# CE842170047_SHEET3.net
KiCad netlist of a schematic drawn in Altium Designer
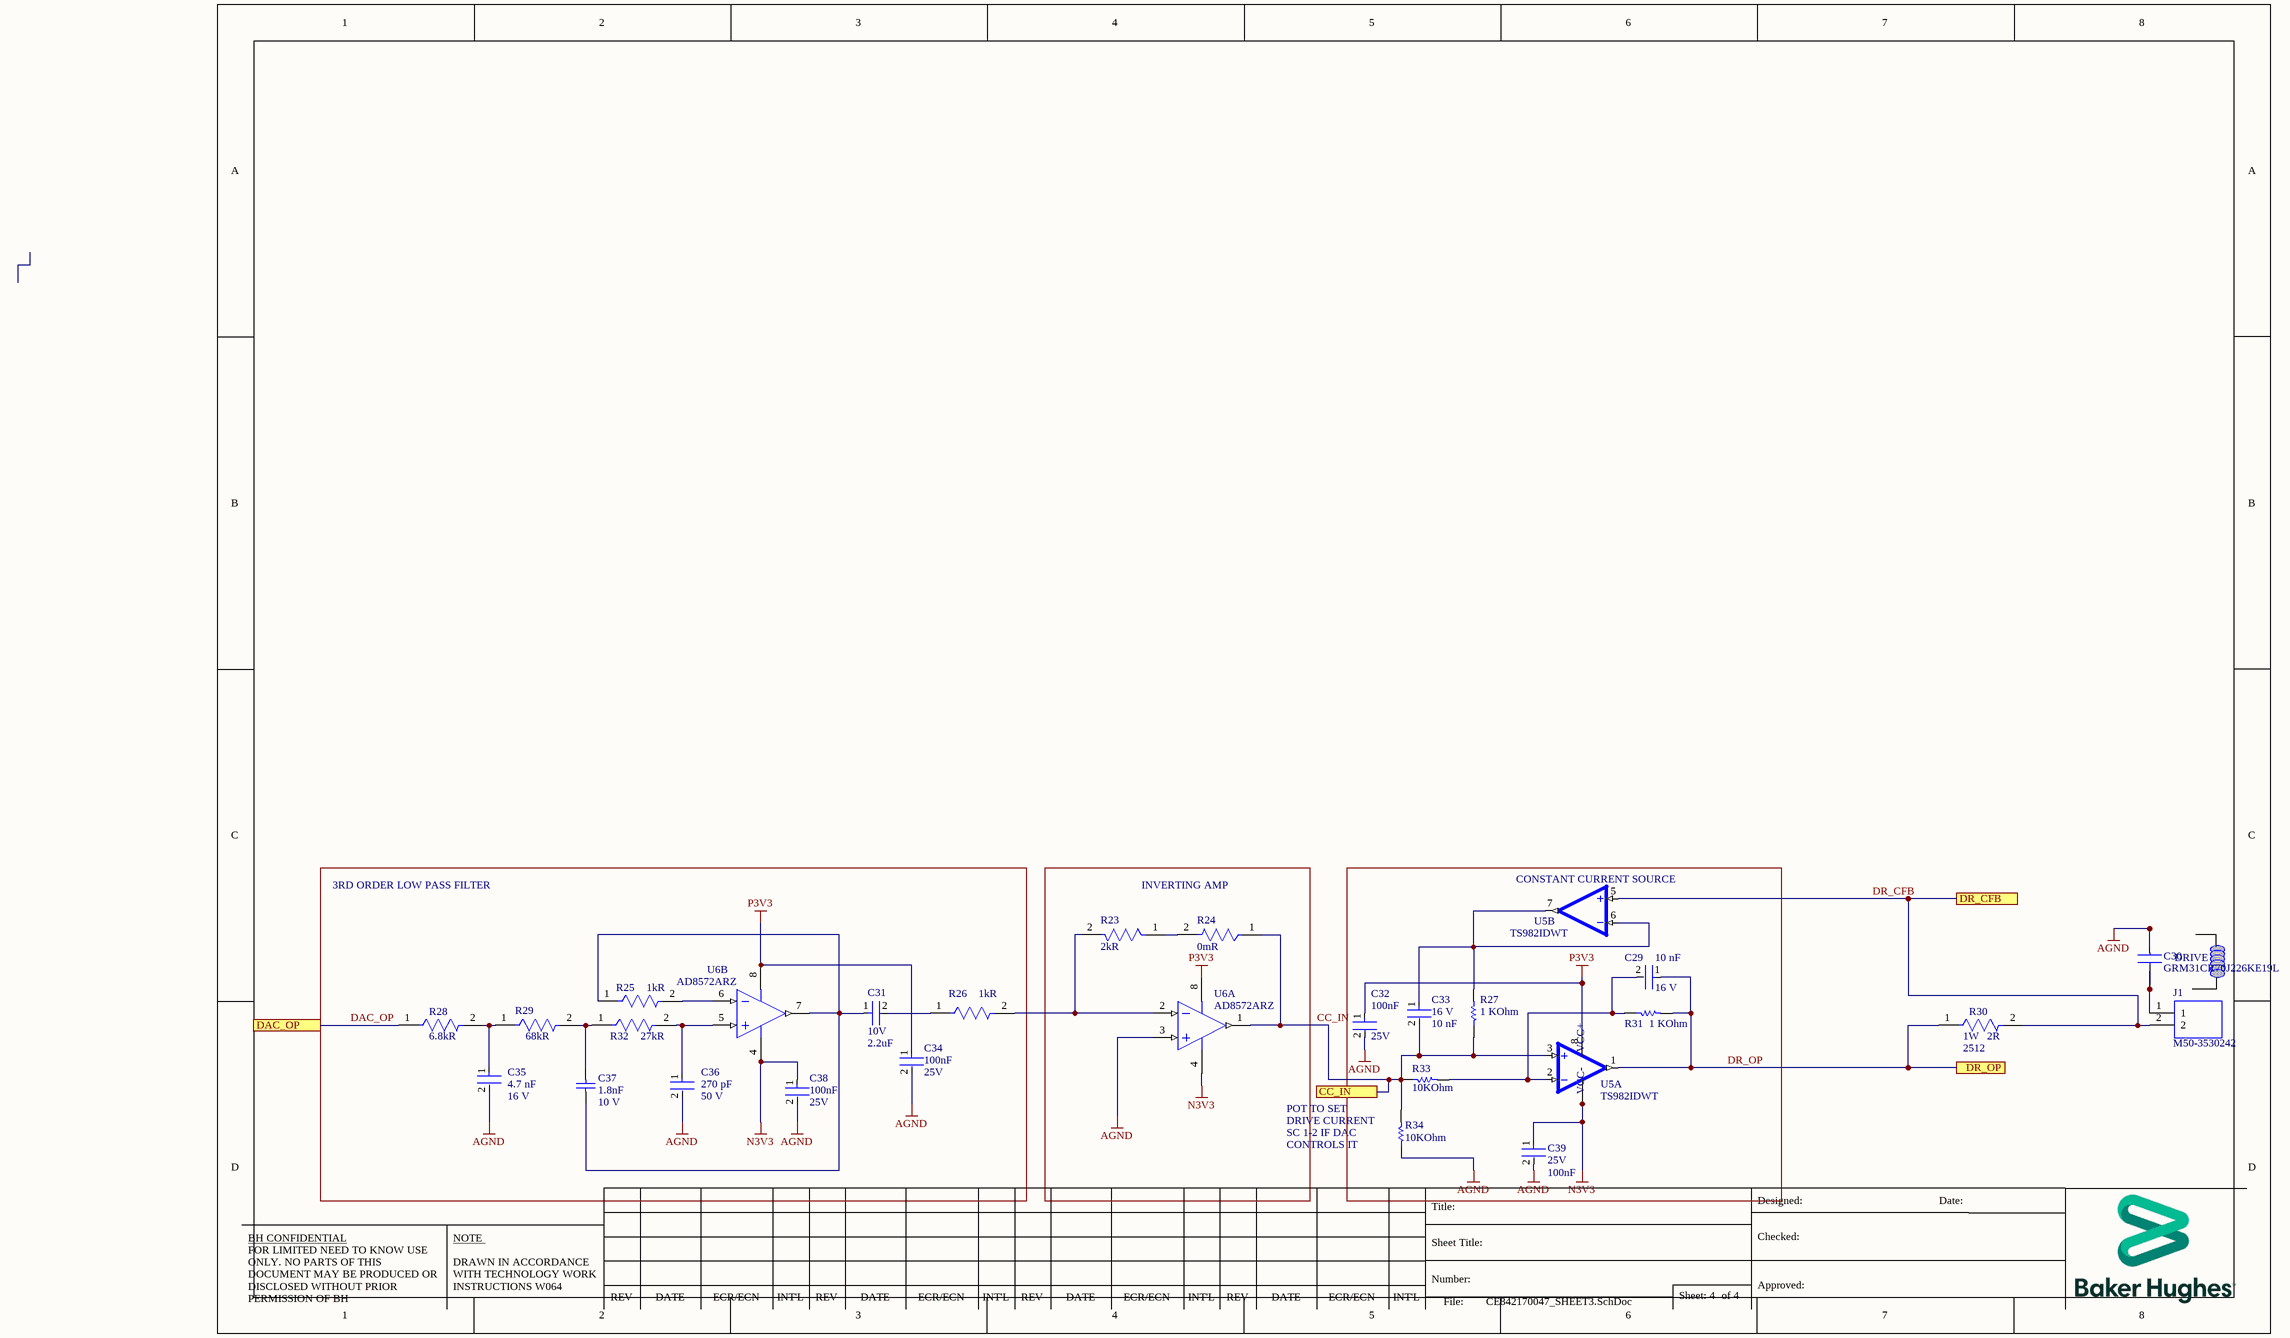
[diagram p0: CE842170047_SHEET3.SchDoc]

(export (version "E")
  (design (tool "Eeschema 10.0.6"))
  (components
    (comp (ref "C29")
      (value "CC0402KRX7R7BB103")
      (footprint "FP-CC0402-MFG")
      (description "CAP CER 10000PF 16V X7R 0402")
      (fields
        (field (name "CAPACITANCE") "10 nF")
        (field (name "TOLERANCE") "0.1")
        (field (name "VOLTAGE RATING") "16 V")
        (field (name "MANUFACTURER") "YAGEO")
      )
      (libsource (lib "Altium Content Vault") (part "11868f565c42a9108669ba33697ecf6"))
    )
    (comp (ref "C30")
      (value "GRM31CR70J226KE19L")
      (footprint "CAPC3216X180N")
      (description "Murata 1206 GRM 22uF Ceramic Multilayer Capacitor, 6.3 V dc, +125C, X7R Dielectric, +/-10% SMD")
      (fields (field (name "MOUSER PART NUMBER") "81-GRM31CR70J226KE9L"))
      (libsource (lib "GRM31CR70J226KE19L") (part "GRM31CR70J226KE19L"))
    )
    (comp (ref "C31")
      (value "CGB3B3X5R1A225M055AB")
      (footprint "FP-CGB3B-IPC_A")
      (description "Multilayer Ceramic Capacitors 2.2uF ±20% 10V X5R SMD 0603")
      (fields
        (field (name "VOLTAGE RATING") "10V")
        (field (name "TOLERANCE") "20%")
        (field (name "CAPACITANCE") "2.2uF")
      )
      (libsource (lib "Altium Content Vault") (part "b4654b650e69147ec39a6b967a45e02"))
    )
    (comp (ref "C32")
      (value "C1005X5R1E104K050BC")
      (footprint "FP-C1005-050-0_05-MFG")
      (description "Multilayer Ceramic Capacitors 100nF ±10% 25V X5R SMD 0402")
      (fields
        (field (name "VOLTAGE RATING (DC)") "25V")
        (field (name "CAPACITANCE") "100nF")
        (field (name "TOLERANCE") "10%")
        (field (name "VOLTAGE") "25V")
      )
      (libsource (lib "Altium Content Vault") (part "b4654b650e69147ec39a6b967a45e02"))
    )
    (comp (ref "C33")
      (value "CC0402KRX7R7BB103")
      (footprint "FP-CC0402-MFG")
      (description "CAP CER 10000PF 16V X7R 0402")
      (fields
        (field (name "CAPACITANCE") "10 nF")
        (field (name "TOLERANCE") "0.1")
        (field (name "VOLTAGE RATING") "16 V")
        (field (name "MANUFACTURER") "YAGEO")
      )
      (libsource (lib "Altium Content Vault") (part "11868f565c42a9108669ba33697ecf6"))
    )
    (comp (ref "C34")
      (value "C1005X5R1E104K050BC")
      (footprint "FP-C1005-050-0_05-MFG")
      (description "Multilayer Ceramic Capacitors 100nF ±10% 25V X5R SMD 0402")
      (fields
        (field (name "VOLTAGE RATING (DC)") "25V")
        (field (name "CAPACITANCE") "100nF")
        (field (name "TOLERANCE") "10%")
        (field (name "VOLTAGE") "25V")
      )
      (libsource (lib "Altium Content Vault") (part "b4654b650e69147ec39a6b967a45e02"))
    )
    (comp (ref "C35")
      (value "CC0402KRX7R7BB472")
      (footprint "FP-CC0402-MFG")
      (description "CAP CER 4700PF 16V X7R 0402")
      (fields
        (field (name "CAPACITANCE") "4.7 nF")
        (field (name "OCTOPART") "https://octopart.com/cc0402krx7r7bb472-yageo-44648962")
        (field (name "MANUFACTURER") "YAGEO")
        (field (name "VOLTAGE RATING") "16 V")
      )
      (libsource (lib "Altium Content Vault") (part "11868f565c42a9108669ba33697ecf6"))
    )
    (comp (ref "C36")
      (value "C0402C271K5RACTU")
      (footprint "FP-C0402-BB-MFG")
      (description "CAP CER 270PF 50V 10% X7R 0402")
      (fields
        (field (name "CAPACITANCE") "270 pF")
        (field (name "VOLTAGE RATING") "50 V")
        (field (name "MANUFACTURER") "Kemet")
        (field (name "OCTOPART") "https://octopart.com/c0402c271k5ractu-kemet-5510096")
      )
      (libsource (lib "Altium Content Vault") (part "b4654b650e69147ec39a6b967a45e02"))
    )
    (comp (ref "C37")
      (value "1.8nF")
      (footprint "CAPC0402(1005)60_N")
      (description "CAP 1.8nF 10V ±5% 0402 (1005 Metric) Thickness 0.6mm SMD")
      (fields
        (field (name "RATED VOLTAGE") "10 V")
        (field (name "TOLERANCE") "Â±5%")
        (field (name "Comment") "CAP 1.8nF 10V 0402(1005)")
      )
      (libsource (lib "Altium Content Vault") (part "CAP"))
    )
    (comp (ref "C38")
      (value "C1005X5R1E104K050BC")
      (footprint "FP-C1005-050-0_05-MFG")
      (description "Multilayer Ceramic Capacitors 100nF ±10% 25V X5R SMD 0402")
      (fields
        (field (name "VOLTAGE RATING (DC)") "25V")
        (field (name "CAPACITANCE") "100nF")
        (field (name "TOLERANCE") "10%")
        (field (name "VOLTAGE") "25V")
      )
      (libsource (lib "Altium Content Vault") (part "b4654b650e69147ec39a6b967a45e02"))
    )
    (comp (ref "C39")
      (value "C1005X5R1E104K050BC")
      (footprint "FP-C1005-050-0_05-MFG")
      (description "Multilayer Ceramic Capacitors 100nF ±10% 25V X5R SMD 0402")
      (fields
        (field (name "VOLTAGE RATING (DC)") "25V")
        (field (name "CAPACITANCE") "100nF")
        (field (name "TOLERANCE") "10%")
        (field (name "VOLTAGE") "25V")
      )
      (libsource (lib "Altium Content Vault") (part "b4654b650e69147ec39a6b967a45e02"))
    )
    (comp (ref "J1")
      (value "M50-3530242")
      (footprint "HDRV2W40P0X127_1X2_254X210X420P")
      (description "Headers & Wire Housings 2 WAY SIL VERT PC TAIL P/HDR")
      (fields (field (name "MOUSER PART NUMBER") "855-M50-3530242"))
      (libsource (lib "M50-3530242") (part "M50-3530242"))
    )
    (comp (ref "R23")
      (value "CRCW04022K00FKED")
      (footprint "FP-CRCW0402-e3-IPC_C")
      (description "RES Thick Film, 2kΩ, 1%, 0.063W, 100ppm/°C, 0402")
      (fields (field (name "TOLERANCE") "1%") (field (name "RESISTANCE") "2kR"))
      (libsource (lib "Altium Content Vault") (part "1029c3af85768c4190bb7ad29bc67b5"))
    )
    (comp (ref "R24")
      (value "MCS04020Z0000ZE000")
      (footprint "FP-MCS0402-MFG")
      (description "RES SMD 1.2K OHM 1% 1/10W 0402")
      (fields (field (name "RESISTANCE") "0mR"))
      (libsource (lib "Altium Content Vault") (part "1029c3af85768c4190bb7ad29bc67b5"))
    )
    (comp (ref "R25")
      (value "CRCW04021K00FKED")
      (footprint "FP-CRCW0402-e3-MFG")
      (description "RES Thick Film, 1kΩ, 1%, 0.063W, 100ppm/°C, 0402")
      (fields (field (name "RESISTANCE") "1kR") (field (name "TOLERANCE") "1%"))
      (libsource (lib "Altium Content Vault") (part "1029c3af85768c4190bb7ad29bc67b5"))
    )
    (comp (ref "R26")
      (value "CRCW04021K00FKED")
      (footprint "FP-CRCW0402-e3-MFG")
      (description "RES Thick Film, 1kΩ, 1%, 0.063W, 100ppm/°C, 0402")
      (fields (field (name "RESISTANCE") "1kR") (field (name "TOLERANCE") "1%"))
      (libsource (lib "Altium Content Vault") (part "1029c3af85768c4190bb7ad29bc67b5"))
    )
    (comp (ref "R27")
      (value "ERJ-2RKF1001X")
      (footprint "RESC1005X40X25NL05T05")
      (description "Chip Resistor, 1 KOhm, +/- 1%, 100 mW, -55 to 155 degC, 0402 (1005 Metric), RoHS, Tape and Reel")
      (fields
        (field (name "MANUFACTURER") "Basic Passives")
        (field (name "TOLERANCE") "1%")
        (field (name "RESISTANCE") "1 KOhm")
      )
      (libsource (lib "Altium Content Vault") (part "RES-2"))
    )
    (comp (ref "R28")
      (value "ERJ-2RKF6801X")
      (footprint "FP-ERJ2RK-IPC_B")
      (description "RES SMD 6.8K OHM 1% 1/10W 0402")
      (fields (field (name "RESISTANCE") "6.8kR") (field (name "TOLERANCE") "1%"))
      (libsource (lib "Altium Content Vault") (part "1029c3af85768c4190bb7ad29bc67b5"))
    )
    (comp (ref "R29")
      (value "CRCW040268K0JNED")
      (footprint "FP-CRCW0402-e3-IPC_C")
      (description "RES Thick Film, 68kΩ, 5%, 0.063W, 200ppm/°C, 0402")
      (fields (field (name "TOLERANCE") "5%") (field (name "RESISTANCE") "68kR"))
      (libsource (lib "Altium Content Vault") (part "1029c3af85768c4190bb7ad29bc67b5"))
    )
    (comp (ref "R30")
      (value "CRCW25122R00FNEG")
      (footprint "FP-CRCW2512-e3-IPC_A")
      (description "RES Thick Film, 2Ω, 1%, 1W, 200ppm/°C, 2512")
      (fields
        (field (name "CASE CODE (IMPERIAL)") "2512")
        (field (name "TOLERANCE") "1%")
        (field (name "RESISTANCE") "2R")
        (field (name "POWER RATING") "1W")
      )
      (libsource (lib "Altium Content Vault") (part "1029c3af85768c4190bb7ad29bc67b5"))
    )
    (comp (ref "R31")
      (value "ERJ-2RKF1001X")
      (footprint "RESC1005X40X25NL05T05")
      (description "Chip Resistor, 1 KOhm, +/- 1%, 100 mW, -55 to 155 degC, 0402 (1005 Metric), RoHS, Tape and Reel")
      (fields
        (field (name "MANUFACTURER") "Basic Passives")
        (field (name "TOLERANCE") "1%")
        (field (name "RESISTANCE") "1 KOhm")
      )
      (libsource (lib "Altium Content Vault") (part "RES-2"))
    )
    (comp (ref "R32")
      (value "CRCW040227K0JNED")
      (footprint "FP-CRCW0402-e3-IPC_C")
      (description "RES Thick Film, 27kΩ, 5%, 0.063W, 200ppm/°C, 0402")
      (fields (field (name "RESISTANCE") "27kR") (field (name "TOLERANCE") "5%"))
      (libsource (lib "Altium Content Vault") (part "1029c3af85768c4190bb7ad29bc67b5"))
    )
    (comp (ref "R33")
      (value "ERJ2RKF1002X")
      (footprint "RESC1005X40X25LL05T05")
      (description "Chip Resistor, 10 KOhm, +/- 1%, 0.1 W, -55 to 155 degC, 0402 (1005 Metric), RoHS, Tape and Reel")
      (fields
        (field (name "RESISTANCE") "10KOhm")
        (field (name "TOLERANCE") "1%")
        (field (name "MANUFACTURER") "Panasonic")
      )
      (libsource (lib "Altium Content Vault") (part "RES-2"))
    )
    (comp (ref "R34")
      (value "ERJ2RKF1002X")
      (footprint "RESC1005X40X25LL05T05")
      (description "Chip Resistor, 10 KOhm, +/- 1%, 0.1 W, -55 to 155 degC, 0402 (1005 Metric), RoHS, Tape and Reel")
      (fields
        (field (name "RESISTANCE") "10KOhm")
        (field (name "TOLERANCE") "1%")
        (field (name "MANUFACTURER") "Panasonic")
      )
      (libsource (lib "Altium Content Vault") (part "RES-2"))
    )
    (comp (ref "U5")
      (value "TS982IDWT")
      (footprint "SOIC127P600X175-9N")
      (libsource (lib "TS982IDWT") (part "TS982IDWT"))
    )
    (comp (ref "U6")
      (value "AD8572ARZ")
      (footprint "ADI-R-8_M")
      (fields (field (name "MANUFACTURER") "Analog Devices") (field (name "GENERIC PART NUMBER") "AD8572"))
      (libsource (lib "Altium Content Vault") (part "ADI-OP29X-R-8"))
    )
  )
  (nets
    (net (code "1") (name "/CC_IN") (class "Default")
      (node (ref "C33") (pin "2") (pinfunction "2_2") (pintype "passive"))
      (node (ref "R24") (pin "1") (pinfunction "1_1") (pintype "passive"))
      (node (ref "R27") (pin "1") (pinfunction "1_1") (pintype "passive"))
      (node (ref "R33") (pin "1") (pinfunction "1_1") (pintype "passive"))
      (node (ref "R34") (pin "2") (pinfunction "2_2") (pintype "passive"))
      (node (ref "U5") (pin "3") (pinfunction "NON_INVERTING_INPUT_1_3") (pintype "input"))
      (node (ref "U6") (pin "1") (pinfunction "OUT_A_1") (pintype "output"))
    )
    (net (code "2") (name "/DAC_OP") (class "Default")
      (node (ref "R28") (pin "1") (pinfunction "1_1") (pintype "passive"))
    )
    (net (code "3") (name "/DR_CFB") (class "Default")
      (node (ref "J1") (pin "2") (pinfunction "2_2") (pintype "passive"))
      (node (ref "R30") (pin "2") (pinfunction "2_2") (pintype "passive"))
      (node (ref "U5") (pin "5") (pinfunction "NON_INVERTING_INPUT_2_5") (pintype "input"))
    )
    (net (code "4") (name "/DR_OP") (class "Default")
      (node (ref "C29") (pin "1") (pinfunction "1_1") (pintype "passive"))
      (node (ref "R30") (pin "1") (pinfunction "1_1") (pintype "passive"))
      (node (ref "R31") (pin "2") (pinfunction "2_2") (pintype "passive"))
      (node (ref "U5") (pin "1") (pinfunction "OUTPUT1_1") (pintype "output"))
    )
    (net (code "5") (name "AGND") (class "Default")
      (node (ref "C30") (pin "2") (pinfunction "2_2") (pintype "passive"))
      (node (ref "C32") (pin "2") (pinfunction "2_2") (pintype "passive"))
      (node (ref "C34") (pin "2") (pinfunction "2_2") (pintype "passive"))
      (node (ref "C35") (pin "2") (pinfunction "2_2") (pintype "passive"))
      (node (ref "C36") (pin "2") (pinfunction "2_2") (pintype "passive"))
      (node (ref "C38") (pin "2") (pinfunction "2_2") (pintype "passive"))
      (node (ref "C39") (pin "2") (pinfunction "2_2") (pintype "passive"))
      (node (ref "R34") (pin "1") (pinfunction "1_1") (pintype "passive"))
      (node (ref "U6") (pin "3") (pinfunction "+IN_A_3") (pintype "input"))
    )
    (net (code "6") (name "N3V3") (class "Default")
      (node (ref "C38") (pin "1") (pinfunction "1_1") (pintype "passive"))
      (node (ref "C39") (pin "1") (pinfunction "1_1") (pintype "passive"))
      (node (ref "U5") (pin "4") (pinfunction "VCC-_4") (pintype "power_in"))
      (node (ref "U5") (pin "9") (pinfunction "VCC-_9") (pintype "power_in"))
      (node (ref "U6") (pin "4") (pinfunction "-V_4") (pintype "power_in"))
    )
    (net (code "7") (name "Net-(C30-Pad1)") (class "Default")
      (node (ref "C30") (pin "1") (pinfunction "1_1") (pintype "passive"))
      (node (ref "J1") (pin "1") (pinfunction "1_1") (pintype "passive"))
    )
    (net (code "8") (name "Net-(C31-Pad2)") (class "Default")
      (node (ref "C31") (pin "2") (pinfunction "2_2") (pintype "passive"))
      (node (ref "R26") (pin "1") (pinfunction "1_1") (pintype "passive"))
    )
    (net (code "9") (name "Net-(C35-Pad1)") (class "Default")
      (node (ref "C35") (pin "1") (pinfunction "1_1") (pintype "passive"))
      (node (ref "R28") (pin "2") (pinfunction "2_2") (pintype "passive"))
      (node (ref "R29") (pin "1") (pinfunction "1_1") (pintype "passive"))
    )
    (net (code "10") (name "Net-(C37-Pad2)") (class "Default")
      (node (ref "C37") (pin "2") (pinfunction "2_2") (pintype "passive"))
      (node (ref "R29") (pin "2") (pinfunction "2_2") (pintype "passive"))
      (node (ref "R32") (pin "1") (pinfunction "1_1") (pintype "passive"))
    )
    (net (code "11") (name "Net-(R23-Pad1)") (class "Default")
      (node (ref "R23") (pin "1") (pinfunction "1_1") (pintype "passive"))
      (node (ref "R24") (pin "2") (pinfunction "2_2") (pintype "passive"))
    )
    (net (code "12") (name "Net-(U5A-INVERTING_INPUT_1)") (class "Default")
      (node (ref "C29") (pin "2") (pinfunction "2_2") (pintype "passive"))
      (node (ref "R31") (pin "1") (pinfunction "1_1") (pintype "passive"))
      (node (ref "R33") (pin "2") (pinfunction "2_2") (pintype "passive"))
      (node (ref "U5") (pin "2") (pinfunction "INVERTING_INPUT_1_2") (pintype "input"))
    )
    (net (code "13") (name "Net-(U5B-INVERTING_INPUT_2)") (class "Default")
      (node (ref "C33") (pin "1") (pinfunction "1_1") (pintype "passive"))
      (node (ref "R27") (pin "2") (pinfunction "2_2") (pintype "passive"))
      (node (ref "U5") (pin "6") (pinfunction "INVERTING_INPUT_2_6") (pintype "input"))
      (node (ref "U5") (pin "7") (pinfunction "OUTPUT2_7") (pintype "output"))
    )
    (net (code "14") (name "Net-(U6A--IN_A)") (class "Default")
      (node (ref "R23") (pin "2") (pinfunction "2_2") (pintype "passive"))
      (node (ref "R26") (pin "2") (pinfunction "2_2") (pintype "passive"))
      (node (ref "U6") (pin "2") (pinfunction "-IN_A_2") (pintype "input"))
    )
    (net (code "15") (name "Net-(U6B-+IN_B)") (class "Default")
      (node (ref "C36") (pin "1") (pinfunction "1_1") (pintype "passive"))
      (node (ref "R32") (pin "2") (pinfunction "2_2") (pintype "passive"))
      (node (ref "U6") (pin "5") (pinfunction "+IN_B_5") (pintype "input"))
    )
    (net (code "16") (name "Net-(U6B--IN_B)") (class "Default")
      (node (ref "R25") (pin "2") (pinfunction "2_2") (pintype "passive"))
      (node (ref "U6") (pin "6") (pinfunction "-IN_B_6") (pintype "input"))
    )
    (net (code "17") (name "Net-(U6B-OUT_B)") (class "Default")
      (node (ref "C31") (pin "1") (pinfunction "1_1") (pintype "passive"))
      (node (ref "C37") (pin "1") (pinfunction "1_1") (pintype "passive"))
      (node (ref "R25") (pin "1") (pinfunction "1_1") (pintype "passive"))
      (node (ref "U6") (pin "7") (pinfunction "OUT_B_7") (pintype "output"))
    )
    (net (code "18") (name "P3V3") (class "Default")
      (node (ref "C32") (pin "1") (pinfunction "1_1") (pintype "passive"))
      (node (ref "C34") (pin "1") (pinfunction "1_1") (pintype "passive"))
      (node (ref "U5") (pin "8") (pinfunction "VCC+_8") (pintype "power_in"))
      (node (ref "U6") (pin "8") (pinfunction "+V_8") (pintype "power_in"))
    )
  )
)
